# Arduino_Mini.net
KiCad netlist of a schematic drawn in EAGLE
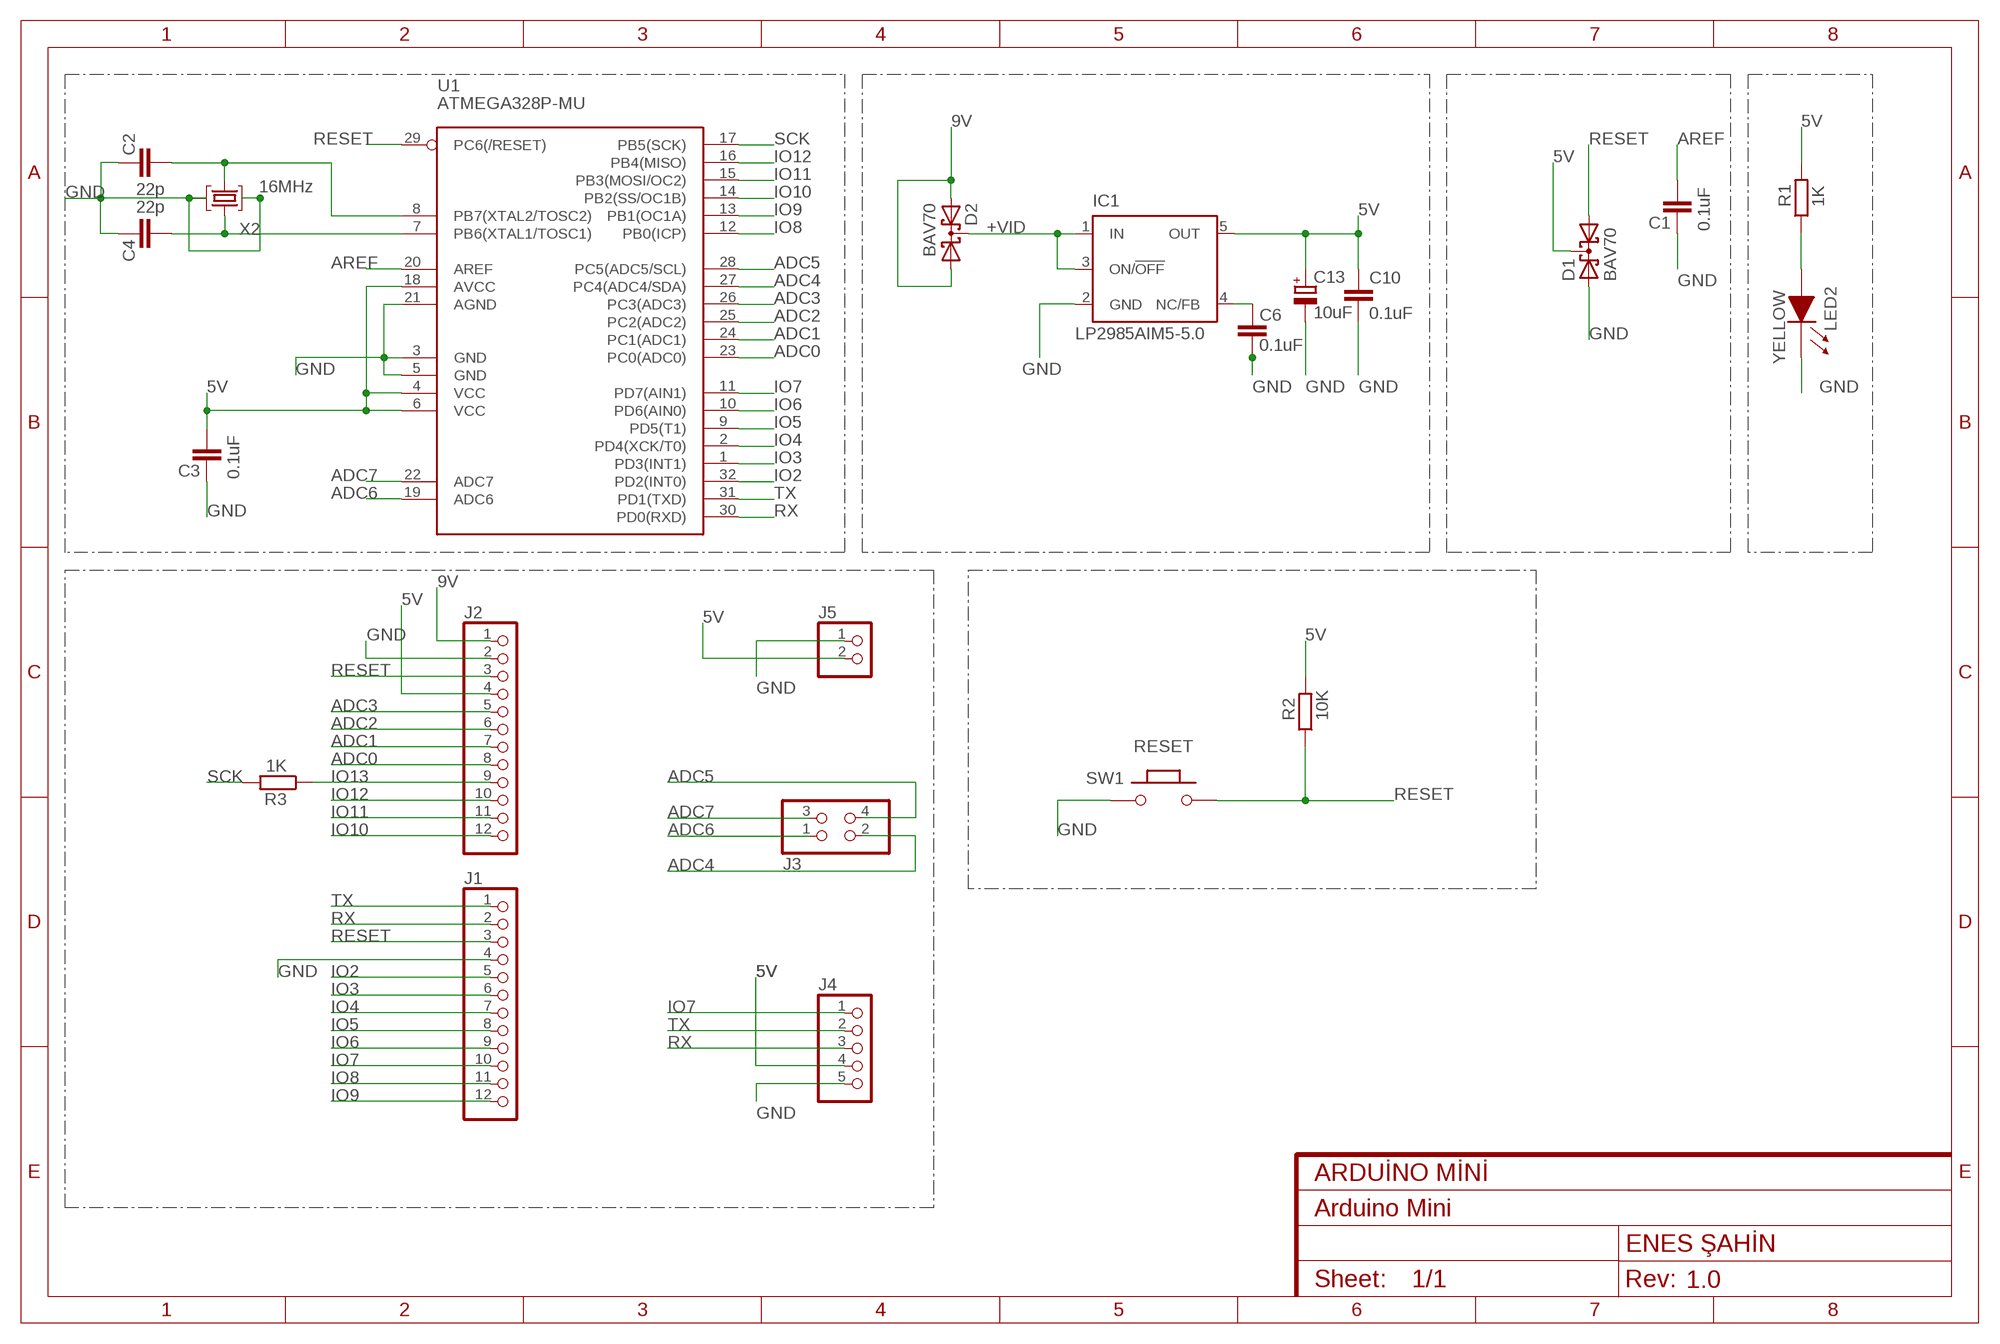
[diagram p0: schematic, sheet 1]

(export (version "E")
  (design (tool "Eeschema 10.0.6"))
  (components
    (comp (ref "C1")
      (value "0.1uF")
      (footprint "eagle-import:C0603-ROUND")
      (libsource (lib "eagle-import") (part "C-EUC0603"))
    )
    (comp (ref "C2")
      (value "22p")
      (footprint "eagle-import:C0603-ROUND")
      (libsource (lib "eagle-import") (part "C-EUC0603"))
    )
    (comp (ref "C3")
      (value "0.1uF")
      (footprint "eagle-import:C0603-ROUND")
      (libsource (lib "eagle-import") (part "C-EUC0603"))
    )
    (comp (ref "C4")
      (value "22p")
      (footprint "eagle-import:C0603-ROUND")
      (libsource (lib "eagle-import") (part "C-EUC0603"))
    )
    (comp (ref "C6")
      (value "0.1uF")
      (footprint "eagle-import:C0603-ROUND")
      (libsource (lib "eagle-import") (part "C-EUC0603"))
    )
    (comp (ref "C10")
      (value "0.1uF")
      (footprint "eagle-import:C0603-ROUND")
      (libsource (lib "eagle-import") (part "C-EUC0603"))
    )
    (comp (ref "C13")
      (value "10uF")
      (footprint "eagle-import:SMC_B")
      (libsource (lib "eagle-import") (part "CPOL-EUSMCB"))
    )
    (comp (ref "D1")
      (value "BAV70")
      (footprint "eagle-import:SOT23")
      (libsource (lib "eagle-import") (part "BAS70-05"))
    )
    (comp (ref "D2")
      (value "BAV70")
      (footprint "eagle-import:SOT23")
      (libsource (lib "eagle-import") (part "BAS70-05"))
    )
    (comp (ref "IC1")
      (value "LP2985AIM5-5.0")
      (footprint "eagle-import:SOT23-DBV")
      (libsource (lib "eagle-import") (part "LP2985-XXDBVR50"))
    )
    (comp (ref "J1")
      (value "PINHD-1X12")
      (footprint "eagle-import:1X12")
      (libsource (lib "eagle-import") (part "PINHD-1X12"))
    )
    (comp (ref "J2")
      (value "PINHD-1X12")
      (footprint "eagle-import:1X12")
      (libsource (lib "eagle-import") (part "PINHD-1X12"))
    )
    (comp (ref "J3")
      (value "PINHD-2X2")
      (footprint "eagle-import:2X02")
      (libsource (lib "eagle-import") (part "PINHD-2X2"))
    )
    (comp (ref "J4")
      (value "PINHD-1X5")
      (footprint "eagle-import:1X5")
      (libsource (lib "eagle-import") (part "PINHD-1X5"))
    )
    (comp (ref "J5")
      (value "PINHD-1X2")
      (footprint "eagle-import:1X2")
      (libsource (lib "eagle-import") (part "PINHD-1X2"))
    )
    (comp (ref "LED2")
      (value "YELLOW")
      (footprint "eagle-import:SMD_LED0805")
      (libsource (lib "eagle-import") (part "MYSMD_LED0805"))
    )
    (comp (ref "R1")
      (value "1K")
      (footprint "eagle-import:R0603-ROUND")
      (libsource (lib "eagle-import") (part "R-EU_R0603"))
    )
    (comp (ref "R2")
      (value "10K")
      (footprint "eagle-import:R0603-ROUND")
      (libsource (lib "eagle-import") (part "R-EU_R0603"))
    )
    (comp (ref "R3")
      (value "1K")
      (footprint "eagle-import:R0603-ROUND")
      (libsource (lib "eagle-import") (part "R-EU_R0603"))
    )
    (comp (ref "SW1")
      (value "RESET")
      (footprint "eagle-import:SMD_157SW")
      (libsource (lib "eagle-import") (part "MYSMD_PB157"))
    )
    (comp (ref "U1")
      (value "ATMEGA328P-MU")
      (footprint "eagle-import:MLF32-M1-A")
      (libsource (lib "eagle-import") (part "ATMEGAXX8-MU"))
    )
    (comp (ref "X2")
      (value "16MHz")
      (footprint "eagle-import:CRYSTAL-3.2-2.5")
      (libsource (lib "eagle-import") (part "CRYSTAL-3.2-2.5"))
    )
  )
  (nets
    (net (code "1") (name "/+VID") (class "Default")
      (node (ref "D2") (pin "3") (pinfunction "C_3") (pintype "passive"))
      (node (ref "IC1") (pin "1") (pinfunction "IN_1") (pintype "input"))
      (node (ref "IC1") (pin "3") (pinfunction "ON/~{OFF}_3") (pintype "input"))
    )
    (net (code "2") (name "/5V") (class "Default")
      (node (ref "C10") (pin "1") (pinfunction "1_1") (pintype "passive"))
      (node (ref "C13") (pin "+") (pinfunction "+_+") (pintype "passive"))
      (node (ref "C3") (pin "1") (pinfunction "1_1") (pintype "passive"))
      (node (ref "D1") (pin "3") (pinfunction "C_3") (pintype "passive"))
      (node (ref "IC1") (pin "5") (pinfunction "OUT_5") (pintype "passive"))
      (node (ref "J2") (pin "4") (pinfunction "4_4") (pintype "passive"))
      (node (ref "J4") (pin "4") (pinfunction "4_4") (pintype "passive"))
      (node (ref "J5") (pin "2") (pinfunction "2_2") (pintype "passive"))
      (node (ref "R1") (pin "2") (pinfunction "2_2") (pintype "passive"))
      (node (ref "R2") (pin "2") (pinfunction "2_2") (pintype "passive"))
      (node (ref "U1") (pin "18") (pinfunction "AVCC_18") (pintype "bidirectional"))
      (node (ref "U1") (pin "4") (pinfunction "VCC_4") (pintype "bidirectional"))
      (node (ref "U1") (pin "6") (pinfunction "VCC_6") (pintype "bidirectional"))
    )
    (net (code "3") (name "/9V") (class "Default")
      (node (ref "D2") (pin "1") (pinfunction "A1_1") (pintype "passive"))
      (node (ref "D2") (pin "2") (pinfunction "A2_2") (pintype "passive"))
      (node (ref "J2") (pin "1") (pinfunction "1_1") (pintype "passive"))
    )
    (net (code "4") (name "/ADC0") (class "Default")
      (node (ref "J2") (pin "8") (pinfunction "8_8") (pintype "passive"))
      (node (ref "U1") (pin "23") (pinfunction "PC0(ADC0)_23") (pintype "bidirectional"))
    )
    (net (code "5") (name "/ADC1") (class "Default")
      (node (ref "J2") (pin "7") (pinfunction "7_7") (pintype "passive"))
      (node (ref "U1") (pin "24") (pinfunction "PC1(ADC1)_24") (pintype "bidirectional"))
    )
    (net (code "6") (name "/ADC2") (class "Default")
      (node (ref "J2") (pin "6") (pinfunction "6_6") (pintype "passive"))
      (node (ref "U1") (pin "25") (pinfunction "PC2(ADC2)_25") (pintype "bidirectional"))
    )
    (net (code "7") (name "/ADC3") (class "Default")
      (node (ref "J2") (pin "5") (pinfunction "5_5") (pintype "passive"))
      (node (ref "U1") (pin "26") (pinfunction "PC3(ADC3)_26") (pintype "bidirectional"))
    )
    (net (code "8") (name "/ADC4") (class "Default")
      (node (ref "J3") (pin "2") (pinfunction "2_2") (pintype "passive"))
      (node (ref "U1") (pin "27") (pinfunction "PC4(ADC4/SDA)_27") (pintype "bidirectional"))
    )
    (net (code "9") (name "/ADC5") (class "Default")
      (node (ref "J3") (pin "4") (pinfunction "4_4") (pintype "passive"))
      (node (ref "U1") (pin "28") (pinfunction "PC5(ADC5/SCL)_28") (pintype "bidirectional"))
    )
    (net (code "10") (name "/ADC6") (class "Default")
      (node (ref "J3") (pin "1") (pinfunction "1_1") (pintype "passive"))
      (node (ref "U1") (pin "19") (pinfunction "ADC6_19") (pintype "bidirectional"))
    )
    (net (code "11") (name "/ADC7") (class "Default")
      (node (ref "J3") (pin "3") (pinfunction "3_3") (pintype "passive"))
      (node (ref "U1") (pin "22") (pinfunction "ADC7_22") (pintype "bidirectional"))
    )
    (net (code "12") (name "/AREF") (class "Default")
      (node (ref "C1") (pin "1") (pinfunction "1_1") (pintype "passive"))
      (node (ref "U1") (pin "20") (pinfunction "AREF_20") (pintype "bidirectional"))
    )
    (net (code "13") (name "/GND") (class "Default")
      (node (ref "C1") (pin "2") (pinfunction "2_2") (pintype "passive"))
      (node (ref "C10") (pin "2") (pinfunction "2_2") (pintype "passive"))
      (node (ref "C13") (pin "-") (pinfunction "-_-") (pintype "passive"))
      (node (ref "C2") (pin "2") (pinfunction "2_2") (pintype "passive"))
      (node (ref "C3") (pin "2") (pinfunction "2_2") (pintype "passive"))
      (node (ref "C4") (pin "2") (pinfunction "2_2") (pintype "passive"))
      (node (ref "C6") (pin "1") (pinfunction "1_1") (pintype "passive"))
      (node (ref "D1") (pin "1") (pinfunction "A1_1") (pintype "passive"))
      (node (ref "IC1") (pin "2") (pinfunction "GND_2") (pintype "power_in"))
      (node (ref "J1") (pin "4") (pinfunction "4_4") (pintype "passive"))
      (node (ref "J2") (pin "2") (pinfunction "2_2") (pintype "passive"))
      (node (ref "J4") (pin "5") (pinfunction "5_5") (pintype "passive"))
      (node (ref "J5") (pin "1") (pinfunction "1_1") (pintype "passive"))
      (node (ref "LED2") (pin "1") (pinfunction "CA_1") (pintype "passive"))
      (node (ref "SW1") (pin "1") (pinfunction "1_1") (pintype "passive"))
      (node (ref "U1") (pin "21") (pinfunction "AGND_21") (pintype "bidirectional"))
      (node (ref "U1") (pin "3") (pinfunction "GND_3") (pintype "bidirectional"))
      (node (ref "U1") (pin "5") (pinfunction "GND_5") (pintype "bidirectional"))
      (node (ref "X2") (pin "2") (pinfunction "GND_2") (pintype "passive"))
      (node (ref "X2") (pin "4") (pinfunction "GND_4") (pintype "passive"))
    )
    (net (code "14") (name "/IO2") (class "Default")
      (node (ref "J1") (pin "5") (pinfunction "5_5") (pintype "passive"))
      (node (ref "U1") (pin "32") (pinfunction "PD2(INT0)_32") (pintype "bidirectional"))
    )
    (net (code "15") (name "/IO3") (class "Default")
      (node (ref "J1") (pin "6") (pinfunction "6_6") (pintype "passive"))
      (node (ref "U1") (pin "1") (pinfunction "PD3(INT1)_1") (pintype "bidirectional"))
    )
    (net (code "16") (name "/IO4") (class "Default")
      (node (ref "J1") (pin "7") (pinfunction "7_7") (pintype "passive"))
      (node (ref "U1") (pin "2") (pinfunction "PD4(XCK/T0)_2") (pintype "bidirectional"))
    )
    (net (code "17") (name "/IO5") (class "Default")
      (node (ref "J1") (pin "8") (pinfunction "8_8") (pintype "passive"))
      (node (ref "U1") (pin "9") (pinfunction "PD5(T1)_9") (pintype "bidirectional"))
    )
    (net (code "18") (name "/IO6") (class "Default")
      (node (ref "J1") (pin "9") (pinfunction "9_9") (pintype "passive"))
      (node (ref "U1") (pin "10") (pinfunction "PD6(AIN0)_10") (pintype "bidirectional"))
    )
    (net (code "19") (name "/IO7") (class "Default")
      (node (ref "J1") (pin "10") (pinfunction "10_10") (pintype "passive"))
      (node (ref "J4") (pin "1") (pinfunction "1_1") (pintype "passive"))
      (node (ref "U1") (pin "11") (pinfunction "PD7(AIN1)_11") (pintype "bidirectional"))
    )
    (net (code "20") (name "/IO8") (class "Default")
      (node (ref "J1") (pin "11") (pinfunction "11_11") (pintype "passive"))
      (node (ref "U1") (pin "12") (pinfunction "PB0(ICP)_12") (pintype "bidirectional"))
    )
    (net (code "21") (name "/IO9") (class "Default")
      (node (ref "J1") (pin "12") (pinfunction "12_12") (pintype "passive"))
      (node (ref "U1") (pin "13") (pinfunction "PB1(OC1A)_13") (pintype "bidirectional"))
    )
    (net (code "22") (name "/IO10") (class "Default")
      (node (ref "J2") (pin "12") (pinfunction "12_12") (pintype "passive"))
      (node (ref "U1") (pin "14") (pinfunction "PB2(SS/OC1B)_14") (pintype "bidirectional"))
    )
    (net (code "23") (name "/IO11") (class "Default")
      (node (ref "J2") (pin "11") (pinfunction "11_11") (pintype "passive"))
      (node (ref "U1") (pin "15") (pinfunction "PB3(MOSI/OC2)_15") (pintype "bidirectional"))
    )
    (net (code "24") (name "/IO12") (class "Default")
      (node (ref "J2") (pin "10") (pinfunction "10_10") (pintype "passive"))
      (node (ref "U1") (pin "16") (pinfunction "PB4(MISO)_16") (pintype "bidirectional"))
    )
    (net (code "25") (name "/IO13") (class "Default")
      (node (ref "J2") (pin "9") (pinfunction "9_9") (pintype "passive"))
      (node (ref "R3") (pin "1") (pinfunction "1_1") (pintype "passive"))
    )
    (net (code "26") (name "/RESET") (class "Default")
      (node (ref "D1") (pin "2") (pinfunction "A2_2") (pintype "passive"))
      (node (ref "J1") (pin "3") (pinfunction "3_3") (pintype "passive"))
      (node (ref "J2") (pin "3") (pinfunction "3_3") (pintype "passive"))
      (node (ref "R2") (pin "1") (pinfunction "1_1") (pintype "passive"))
      (node (ref "SW1") (pin "2") (pinfunction "2_2") (pintype "passive"))
      (node (ref "U1") (pin "29") (pinfunction "PC6(/RESET)_29") (pintype "bidirectional"))
    )
    (net (code "27") (name "/RX") (class "Default")
      (node (ref "J1") (pin "2") (pinfunction "2_2") (pintype "passive"))
      (node (ref "J4") (pin "3") (pinfunction "3_3") (pintype "passive"))
      (node (ref "U1") (pin "30") (pinfunction "PD0(RXD)_30") (pintype "bidirectional"))
    )
    (net (code "28") (name "/SCK") (class "Default")
      (node (ref "R3") (pin "2") (pinfunction "2_2") (pintype "passive"))
      (node (ref "U1") (pin "17") (pinfunction "PB5(SCK)_17") (pintype "bidirectional"))
    )
    (net (code "29") (name "/TX") (class "Default")
      (node (ref "J1") (pin "1") (pinfunction "1_1") (pintype "passive"))
      (node (ref "J4") (pin "2") (pinfunction "2_2") (pintype "passive"))
      (node (ref "U1") (pin "31") (pinfunction "PD1(TXD)_31") (pintype "bidirectional"))
    )
    (net (code "30") (name "Net-(IC1-NC{slash}FB)") (class "Default")
      (node (ref "C6") (pin "2") (pinfunction "2_2") (pintype "passive"))
      (node (ref "IC1") (pin "4") (pinfunction "NC/FB_4") (pintype "passive"))
    )
    (net (code "31") (name "Net-(LED2-AN)") (class "Default")
      (node (ref "LED2") (pin "2") (pinfunction "AN_2") (pintype "passive"))
      (node (ref "R1") (pin "1") (pinfunction "1_1") (pintype "passive"))
    )
    (net (code "32") (name "Net-(U1-PB6(XTAL1{slash}TOSC1))") (class "Default")
      (node (ref "C4") (pin "1") (pinfunction "1_1") (pintype "passive"))
      (node (ref "U1") (pin "7") (pinfunction "PB6(XTAL1/TOSC1)_7") (pintype "bidirectional"))
      (node (ref "X2") (pin "1") (pinfunction "C1_1") (pintype "passive"))
    )
    (net (code "33") (name "Net-(U1-PB7(XTAL2{slash}TOSC2))") (class "Default")
      (node (ref "C2") (pin "1") (pinfunction "1_1") (pintype "passive"))
      (node (ref "U1") (pin "8") (pinfunction "PB7(XTAL2/TOSC2)_8") (pintype "bidirectional"))
      (node (ref "X2") (pin "3") (pinfunction "C2_3") (pintype "passive"))
    )
  )
)
